# Power_supply.net
KiCad netlist of a schematic drawn in Altium Designer
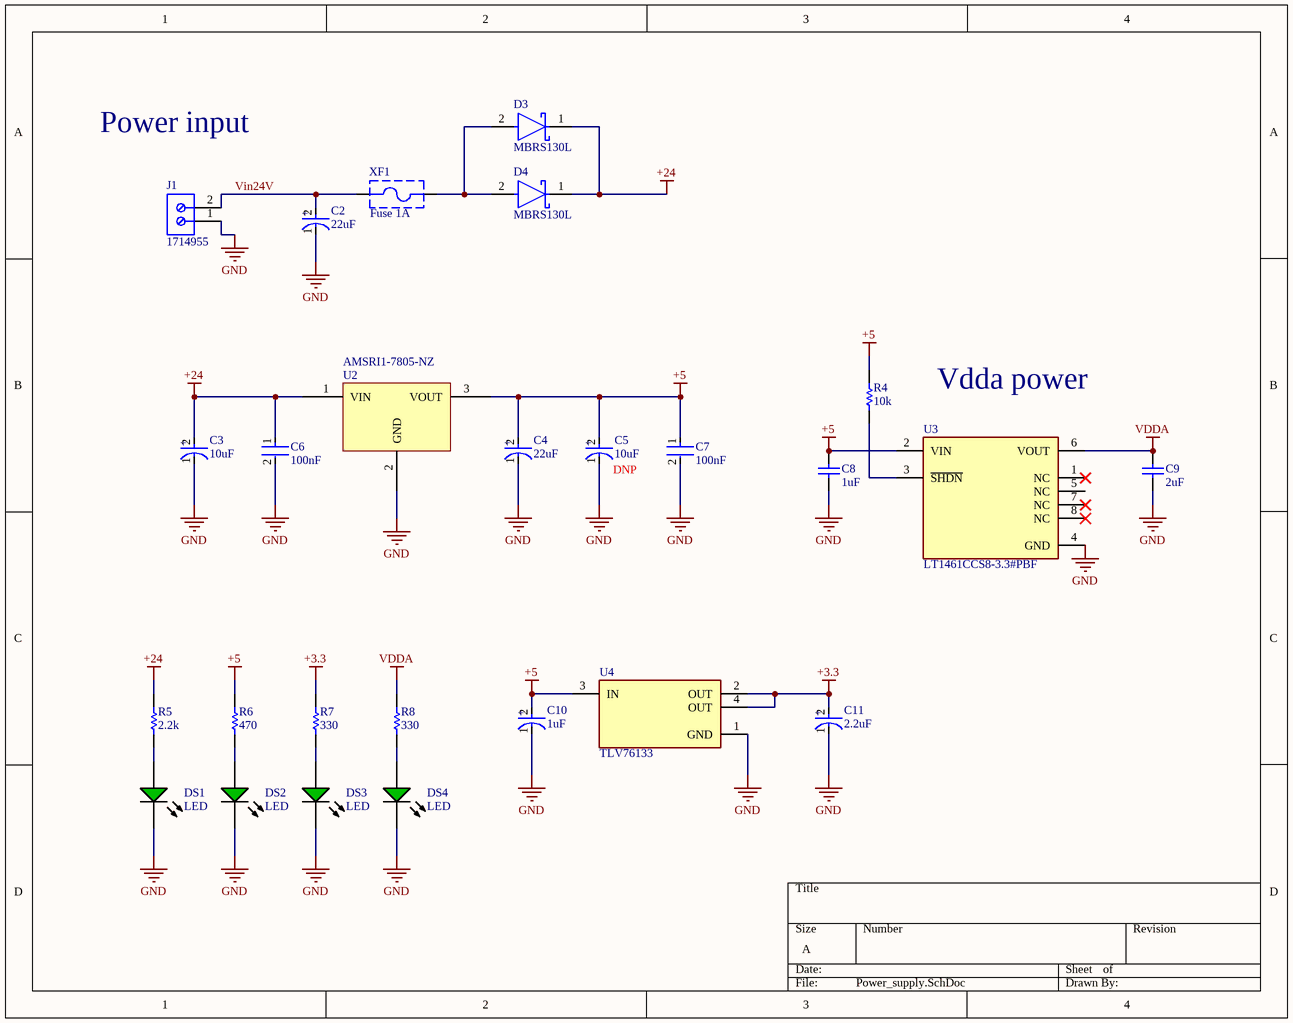
[diagram p0: Power_supply.SchDoc]

(export (version "E")
  (design (tool "Eeschema 10.0.6"))
  (components
    (comp (ref "C2")
      (value "22uF")
      (footprint "FP-FCE-MFG")
      (description "CAP ALUM 22UF 20% 50V SMD")
      (fields (field (name "VOLTAGE") "50V") (field (name "TOLERANCE") "20%"))
      (libsource (lib "Altium Content Vault") (part "a00bbbee19879c290e62620ae7e47b1"))
    )
    (comp (ref "C3")
      (value "10uF")
      (footprint "FP-FKD-MFG")
      (description "CAP ALUM 10UF 20% 50V SMD")
      (fields (field (name "VOLTAGE") "50V") (field (name "TOLERANCE") "20%"))
      (libsource (lib "Altium Content Vault") (part "203bc49f2ac43e59fd269a8c329ed05"))
    )
    (comp (ref "C4")
      (value "22uF")
      (footprint "FP-FCE-MFG")
      (description "CAP ALUM 22UF 20% 50V SMD")
      (fields (field (name "VOLTAGE") "50V") (field (name "TOLERANCE") "20%"))
      (libsource (lib "Altium Content Vault") (part "a00bbbee19879c290e62620ae7e47b1"))
    )
    (comp (ref "C5")
      (value "10uF")
      (footprint "FP-FKD-MFG")
      (description "CAP ALUM 10UF 20% 50V SMD")
      (fields (field (name "VOLTAGE") "50V") (field (name "TOLERANCE") "20%"))
      (libsource (lib "Altium Content Vault") (part "203bc49f2ac43e59fd269a8c329ed05"))
    )
    (comp (ref "C6")
      (value "100nF")
      (footprint "FP-0805-L_2_01_0_2-W_1_25-IPC_B")
      (description "General Purpose Ceramic Capacitor, 0805, 10nF, 10%, X7R, 15%, 100V")
      (fields (field (name "VOLTAGE") "100V") (field (name "TOLERANCE") "10%"))
      (libsource (lib "Altium Content Vault") (part "b4654b650e69147ec39a6b967a45e02"))
    )
    (comp (ref "C7")
      (value "100nF")
      (footprint "FP-0805-L_2_01_0_2-W_1_25-IPC_B")
      (description "General Purpose Ceramic Capacitor, 0805, 10nF, 10%, X7R, 15%, 100V")
      (fields (field (name "VOLTAGE") "100V") (field (name "TOLERANCE") "10%"))
      (libsource (lib "Altium Content Vault") (part "b4654b650e69147ec39a6b967a45e02"))
    )
    (comp (ref "C8")
      (value "1uF")
      (footprint "CAPC2013X140X50LL20T25")
      (fields (field (name "PART NUMBER") "C0805C105K3RACTU") (field (name "MANUFACTURER") "Kemet"))
      (libsource (lib "Altium Content Vault") (part "CAP"))
    )
    (comp (ref "C9")
      (value "2uF")
      (footprint "CAPC2013X140X50LL20T25")
      (fields (field (name "PART NUMBER") "C0805C105K3RACTU") (field (name "MANUFACTURER") "Kemet"))
      (libsource (lib "Altium Content Vault") (part "CAP"))
    )
    (comp (ref "C10")
      (value "1uF")
      (footprint "FP-FKD-MFG")
      (description "CAP ALUM 10UF 20% 50V SMD")
      (fields (field (name "VOLTAGE") "50V") (field (name "TOLERANCE") "20%"))
      (libsource (lib "Altium Content Vault") (part "203bc49f2ac43e59fd269a8c329ed05"))
    )
    (comp (ref "C11")
      (value "2.2uF")
      (footprint "FP-FKD-MFG")
      (description "CAP ALUM 10UF 20% 50V SMD")
      (fields (field (name "VOLTAGE") "50V") (field (name "TOLERANCE") "20%"))
      (libsource (lib "Altium Content Vault") (part "203bc49f2ac43e59fd269a8c329ed05"))
    )
    (comp (ref "D3")
      (value "MBRS130L")
      (footprint "FP-403AF-MFG")
      (description "MBRS130L Rectifier Diode, Schottky, 1 Phase, 1 Element, 2A, 30V V(RRM), Silicon, DO-214AA")
      (libsource (lib "Altium Content Vault") (part "1d6ec82d83fb6aee721767c19dac4b9"))
    )
    (comp (ref "D4")
      (value "MBRS130L")
      (footprint "FP-403AF-MFG")
      (description "MBRS130L Rectifier Diode, Schottky, 1 Phase, 1 Element, 2A, 30V V(RRM), Silicon, DO-214AA")
      (libsource (lib "Altium Content Vault") (part "1d6ec82d83fb6aee721767c19dac4b9"))
    )
    (comp (ref "DS1")
      (value "LED")
      (footprint "AVAG-HSMX-C170_V")
      (description "Chip LED, Green, 2.2 V, -40 to 85 degC, 2-Pin SMD, Pb-Free, Tape and Reel")
      (fields (field (name "MANUFACTURER") "Avago"))
      (libsource (lib "Altium Content Vault") (part "LED_GREEN_A1K2-2"))
    )
    (comp (ref "DS2")
      (value "LED")
      (footprint "AVAG-HSMX-C170_V")
      (description "Chip LED, Green, 2.2 V, -40 to 85 degC, 2-Pin SMD, Pb-Free, Tape and Reel")
      (fields (field (name "MANUFACTURER") "Avago"))
      (libsource (lib "Altium Content Vault") (part "LED_GREEN_A1K2-2"))
    )
    (comp (ref "DS3")
      (value "LED")
      (footprint "AVAG-HSMX-C170_V")
      (description "Chip LED, Green, 2.2 V, -40 to 85 degC, 2-Pin SMD, Pb-Free, Tape and Reel")
      (fields (field (name "MANUFACTURER") "Avago"))
      (libsource (lib "Altium Content Vault") (part "LED_GREEN_A1K2-2"))
    )
    (comp (ref "DS4")
      (value "LED")
      (footprint "AVAG-HSMX-C170_V")
      (description "Chip LED, Green, 2.2 V, -40 to 85 degC, 2-Pin SMD, Pb-Free, Tape and Reel")
      (fields (field (name "MANUFACTURER") "Avago"))
      (libsource (lib "Altium Content Vault") (part "LED_GREEN_A1K2-2"))
    )
    (comp (ref "J1")
      (value "1714955")
      (footprint "PHOE-1714955_V")
      (description "PC Terminal Block, Pitch 6.35 mm, 1 x 2 Position, Height 21.5 mm, Tail Lenght 5.1 mm, RoHS, Bulk")
      (fields (field (name "MANUFACTURER") "Phoenix Contact"))
      (libsource (lib "Altium Content Vault") (part "CN-1P-F-TB2"))
    )
    (comp (ref "R4")
      (value "10k")
      (footprint "RESC2013X50X30LL20T20")
      (fields (field (name "MANUFACTURER") "Vishay Dale") (field (name "PART NUMBER") "CRCW08050000Z0EA"))
      (libsource (lib "Altium Content Vault") (part "RES"))
    )
    (comp (ref "R5")
      (value "2.2k")
      (footprint "RESC2013X50X30LL20T20")
      (fields (field (name "MANUFACTURER") "Vishay Dale") (field (name "PART NUMBER") "CRCW08050000Z0EA"))
      (libsource (lib "Altium Content Vault") (part "RES"))
    )
    (comp (ref "R6")
      (value "470")
      (footprint "RESC2013X50X30LL20T20")
      (fields (field (name "MANUFACTURER") "Vishay Dale") (field (name "PART NUMBER") "CRCW08050000Z0EA"))
      (libsource (lib "Altium Content Vault") (part "RES"))
    )
    (comp (ref "R7")
      (value "330")
      (footprint "RESC2013X50X30LL20T20")
      (fields (field (name "MANUFACTURER") "Vishay Dale") (field (name "PART NUMBER") "CRCW08050000Z0EA"))
      (libsource (lib "Altium Content Vault") (part "RES"))
    )
    (comp (ref "R8")
      (value "330")
      (footprint "RESC2013X50X30LL20T20")
      (fields (field (name "MANUFACTURER") "Vishay Dale") (field (name "PART NUMBER") "CRCW08050000Z0EA"))
      (libsource (lib "Altium Content Vault") (part "RES"))
    )
    (comp (ref "U2")
      (value "AMSRI1-7805-NZ")
      (footprint "SIP750W46P254L1400H1010Q3")
      (description "AMSRI1-7805-NZ, 5V / 1A DC output converter")
      (libsource (lib "Schematic_library") (part "AMSRI1-7805-NZ"))
    )
    (comp (ref "U3")
      (value "LT1461CCS8-3.3#PBF")
      (footprint "FP-S8-8-05-08-1610-IPC_A")
      (description "IC VREF SERIES 0.08% 8SOIC")
      (fields (field (name "TOLERANCE") "0.08%"))
      (libsource (lib "Altium Content Vault") (part "89c9ffe9d60ac6c934f8caf59899f03"))
    )
    (comp (ref "U4")
      (value "TLV76133")
      (footprint "FP-DCY0004A-MFG")
      (description "TLV76133 1-A 16-V high-PSRR linear voltage regulator 4-SOT-223 -40 to 125")
      (libsource (lib "Altium Content Vault") (part "991ffb903c51cf6179ce9942c0606aa"))
    )
    (comp (ref "XF1")
      (value "Fuse 1A")
      (footprint "696106003002")
      (libsource (lib "Altium Content Vault") (part "Fuse Holder"))
    )
  )
  (nets
    (net (code "1") (name "+3.3") (class "Default")
      (node (ref "C11") (pin "2") (pinfunction "A_2") (pintype "passive"))
      (node (ref "R7") (pin "2") (pinfunction "2_2") (pintype "passive"))
      (node (ref "U4") (pin "2") (pinfunction "OUT_2") (pintype "passive"))
      (node (ref "U4") (pin "4") (pinfunction "OUT_4") (pintype "passive"))
    )
    (net (code "2") (name "+5") (class "Default")
      (node (ref "C10") (pin "2") (pinfunction "A_2") (pintype "passive"))
      (node (ref "C4") (pin "2") (pinfunction "A_2") (pintype "passive"))
      (node (ref "C5") (pin "2") (pinfunction "A_2") (pintype "passive"))
      (node (ref "C7") (pin "1") (pinfunction "1_1") (pintype "passive"))
      (node (ref "C8") (pin "2") (pinfunction "2_2") (pintype "passive"))
      (node (ref "R4") (pin "2") (pinfunction "2_2") (pintype "passive"))
      (node (ref "R6") (pin "2") (pinfunction "2_2") (pintype "passive"))
      (node (ref "U2") (pin "3") (pinfunction "VOUT_3") (pintype "passive"))
      (node (ref "U3") (pin "2") (pinfunction "VIN_2") (pintype "power_in"))
      (node (ref "U4") (pin "3") (pinfunction "IN_3") (pintype "power_in"))
    )
    (net (code "3") (name "+24") (class "Default")
      (node (ref "C3") (pin "2") (pinfunction "A_2") (pintype "passive"))
      (node (ref "C6") (pin "1") (pinfunction "1_1") (pintype "passive"))
      (node (ref "D3") (pin "1") (pinfunction "C_1") (pintype "passive"))
      (node (ref "D4") (pin "1") (pinfunction "C_1") (pintype "passive"))
      (node (ref "R5") (pin "2") (pinfunction "2_2") (pintype "passive"))
      (node (ref "U2") (pin "1") (pinfunction "VIN_1") (pintype "passive"))
    )
    (net (code "4") (name "/Vin24V") (class "Default")
      (node (ref "C2") (pin "2") (pinfunction "A_2") (pintype "passive"))
      (node (ref "J1") (pin "2") (pinfunction "2_2") (pintype "passive"))
      (node (ref "XF1") (pin "1") (pinfunction "1_1") (pintype "passive"))
    )
    (net (code "5") (name "GND") (class "Default")
      (node (ref "C10") (pin "1") (pinfunction "C_1") (pintype "passive"))
      (node (ref "C11") (pin "1") (pinfunction "C_1") (pintype "passive"))
      (node (ref "C2") (pin "1") (pinfunction "C_1") (pintype "passive"))
      (node (ref "C3") (pin "1") (pinfunction "C_1") (pintype "passive"))
      (node (ref "C4") (pin "1") (pinfunction "C_1") (pintype "passive"))
      (node (ref "C5") (pin "1") (pinfunction "C_1") (pintype "passive"))
      (node (ref "C6") (pin "2") (pinfunction "2_2") (pintype "passive"))
      (node (ref "C7") (pin "2") (pinfunction "2_2") (pintype "passive"))
      (node (ref "C8") (pin "1") (pinfunction "1_1") (pintype "passive"))
      (node (ref "C9") (pin "1") (pinfunction "1_1") (pintype "passive"))
      (node (ref "DS1") (pin "2") (pinfunction "K_2") (pintype "passive"))
      (node (ref "DS2") (pin "2") (pinfunction "K_2") (pintype "passive"))
      (node (ref "DS3") (pin "2") (pinfunction "K_2") (pintype "passive"))
      (node (ref "DS4") (pin "2") (pinfunction "K_2") (pintype "passive"))
      (node (ref "J1") (pin "1") (pinfunction "1_1") (pintype "passive"))
      (node (ref "U2") (pin "2") (pinfunction "GND_2") (pintype "passive"))
      (node (ref "U3") (pin "4") (pinfunction "GND_4") (pintype "power_in"))
      (node (ref "U4") (pin "1") (pinfunction "GND_1") (pintype "power_in"))
    )
    (net (code "6") (name "Net-(D3-A)") (class "Default")
      (node (ref "D3") (pin "2") (pinfunction "A_2") (pintype "passive"))
      (node (ref "D4") (pin "2") (pinfunction "A_2") (pintype "passive"))
      (node (ref "XF1") (pin "2") (pinfunction "2_2") (pintype "passive"))
    )
    (net (code "7") (name "Net-(DS1-A)") (class "Default")
      (node (ref "DS1") (pin "1") (pinfunction "A_1") (pintype "passive"))
      (node (ref "R5") (pin "1") (pinfunction "1_1") (pintype "passive"))
    )
    (net (code "8") (name "Net-(DS2-A)") (class "Default")
      (node (ref "DS2") (pin "1") (pinfunction "A_1") (pintype "passive"))
      (node (ref "R6") (pin "1") (pinfunction "1_1") (pintype "passive"))
    )
    (net (code "9") (name "Net-(DS3-A)") (class "Default")
      (node (ref "DS3") (pin "1") (pinfunction "A_1") (pintype "passive"))
      (node (ref "R7") (pin "1") (pinfunction "1_1") (pintype "passive"))
    )
    (net (code "10") (name "Net-(DS4-A)") (class "Default")
      (node (ref "DS4") (pin "1") (pinfunction "A_1") (pintype "passive"))
      (node (ref "R8") (pin "1") (pinfunction "1_1") (pintype "passive"))
    )
    (net (code "11") (name "Net-(U3-~{SHDN})") (class "Default")
      (node (ref "R4") (pin "1") (pinfunction "1_1") (pintype "passive"))
      (node (ref "U3") (pin "3") (pinfunction "~{SHDN}_3") (pintype "passive"))
    )
    (net (code "12") (name "VDDA") (class "Default")
      (node (ref "C9") (pin "2") (pinfunction "2_2") (pintype "passive"))
      (node (ref "R8") (pin "2") (pinfunction "2_2") (pintype "passive"))
      (node (ref "U3") (pin "6") (pinfunction "VOUT_6") (pintype "power_in"))
    )
    (net (code "13") (name "unconnected-(U3-NC-Pad1)") (class "Default")
      (node (ref "U3") (pin "1") (pinfunction "NC_1") (pintype "passive+no_connect"))
    )
    (net (code "14") (name "unconnected-(U3-NC-Pad5)") (class "Default")
      (node (ref "U3") (pin "5") (pinfunction "NC_5") (pintype "passive"))
    )
    (net (code "15") (name "unconnected-(U3-NC-Pad7)") (class "Default")
      (node (ref "U3") (pin "7") (pinfunction "NC_7") (pintype "passive+no_connect"))
    )
    (net (code "16") (name "unconnected-(U3-NC-Pad8)") (class "Default")
      (node (ref "U3") (pin "8") (pinfunction "NC_8") (pintype "passive+no_connect"))
    )
  )
)
